# khanh_PB_ip5306_1_1.net
KiCad netlist of a schematic drawn in EAGLE
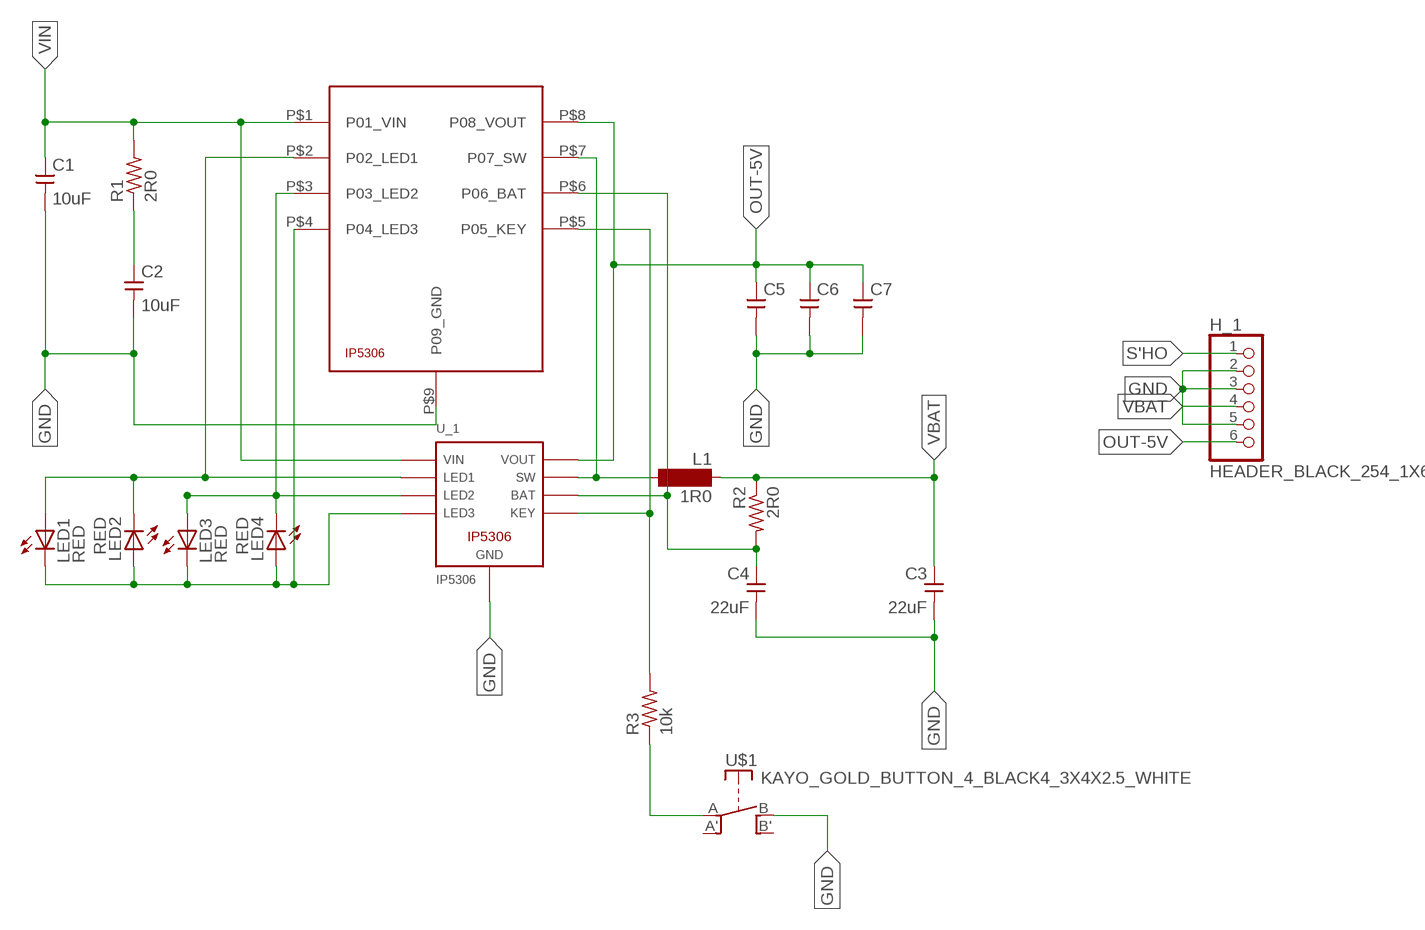
[diagram p0: schematic, sheet 1]

(export (version "E")
  (design (tool "Eeschema 10.0.6"))
  (components
    (comp (ref "C1")
      (value "10uF")
      (footprint "eagle-import:C1206")
      (libsource (lib "eagle-import") (part "KAYO_CAP_CERAMIC_120610UF"))
    )
    (comp (ref "C2")
      (value "10uF")
      (footprint "eagle-import:C1206")
      (libsource (lib "eagle-import") (part "KAYO_CAP_CERAMIC_120610UF"))
    )
    (comp (ref "C3")
      (value "22uF")
      (footprint "eagle-import:C1206")
      (libsource (lib "eagle-import") (part "KAYO_CAP_CERAMIC_120622UF"))
    )
    (comp (ref "C4")
      (value "22uF")
      (footprint "eagle-import:C1206")
      (libsource (lib "eagle-import") (part "KAYO_CAP_CERAMIC_120622UF"))
    )
    (comp (ref "C5")
      (value "KAYO_CAP_CERAMIC22UF_KXN_0603")
      (footprint "eagle-import:KXN_C0603")
      (libsource (lib "eagle-import") (part "KAYO_CAP_CERAMIC_KXN_060322UF"))
    )
    (comp (ref "C6")
      (value "KAYO_CAP_CERAMIC22UF_KXN_0603")
      (footprint "eagle-import:KXN_C0603")
      (libsource (lib "eagle-import") (part "KAYO_CAP_CERAMIC_KXN_060322UF"))
    )
    (comp (ref "C7")
      (value "KAYO_CAP_CERAMIC22UF_KXN_0603")
      (footprint "eagle-import:KXN_C0603")
      (libsource (lib "eagle-import") (part "KAYO_CAP_CERAMIC_KXN_060322UF"))
    )
    (comp (ref "H_1")
      (value "HEADER_BLACK_254_1X6")
      (footprint "eagle-import:HEADER_1X6_254")
      (libsource (lib "eagle-import") (part "KXN_HEADER_1X6"))
    )
    (comp (ref "L1")
      (value "1R0")
      (footprint "eagle-import:CKST_0603_0630_PACK")
      (libsource (lib "eagle-import") (part "INDUCTOR_FEEDER_KAYO_0650"))
    )
    (comp (ref "LED1")
      (value "RED")
      (footprint "eagle-import:KXN_LED_0603")
      (libsource (lib "eagle-import") (part "KAYO_LED_KXN_LED_0603_RED"))
    )
    (comp (ref "LED2")
      (value "RED")
      (footprint "eagle-import:KXN_LED_0603")
      (libsource (lib "eagle-import") (part "KAYO_LED_KXN_LED_0603_RED"))
    )
    (comp (ref "LED3")
      (value "RED")
      (footprint "eagle-import:KXN_LED_0603")
      (libsource (lib "eagle-import") (part "KAYO_LED_KXN_LED_0603_RED"))
    )
    (comp (ref "LED4")
      (value "RED")
      (footprint "eagle-import:KXN_LED_0603")
      (libsource (lib "eagle-import") (part "KAYO_LED_KXN_LED_0603_RED"))
    )
    (comp (ref "R1")
      (value "2R0")
      (footprint "eagle-import:R0603")
      (libsource (lib "eagle-import") (part "R-US_R0603"))
    )
    (comp (ref "R2")
      (value "2R0")
      (footprint "eagle-import:R0603")
      (libsource (lib "eagle-import") (part "R-US_R0603"))
    )
    (comp (ref "R3")
      (value "10k")
      (footprint "eagle-import:R0603")
      (libsource (lib "eagle-import") (part "R-US_R0603"))
    )
    (comp (ref "U$1")
      (value "KAYO_GOLD_BUTTON_4_BLACK4_3X4X2.5_WHITE")
      (footprint "eagle-import:KXN_BUTTON_3_4_2.5MM")
      (libsource (lib "eagle-import") (part "KAYO_GOLD_BUTTON_44_3X4X2.5_WHITE_BLACK"))
    )
    (comp (ref "U$2")
      (value "IP5306")
      (footprint "eagle-import:IP5306")
      (libsource (lib "eagle-import") (part "IP5306"))
    )
    (comp (ref "U_1")
      (value "IP5306")
      (footprint "eagle-import:ESOP8")
      (libsource (lib "eagle-import") (part "IP5306_1"))
    )
  )
  (nets
    (net (code "1") (name "GND") (class "Default")
      (node (ref "C1") (pin "2") (pinfunction "-_2") (pintype "passive"))
      (node (ref "C2") (pin "2") (pinfunction "-_2") (pintype "passive"))
      (node (ref "C3") (pin "2") (pinfunction "-_2") (pintype "passive"))
      (node (ref "C4") (pin "2") (pinfunction "-_2") (pintype "passive"))
      (node (ref "C5") (pin "2") (pinfunction "-_2") (pintype "passive"))
      (node (ref "C6") (pin "2") (pinfunction "-_2") (pintype "passive"))
      (node (ref "C7") (pin "2") (pinfunction "-_2") (pintype "passive"))
      (node (ref "H_1") (pin "2") (pinfunction "2_2") (pintype "passive"))
      (node (ref "H_1") (pin "3") (pinfunction "3_3") (pintype "passive"))
      (node (ref "H_1") (pin "5") (pinfunction "5_5") (pintype "passive"))
      (node (ref "U$1") (pin "B") (pinfunction "B_B") (pintype "passive"))
      (node (ref "U$2") (pin "P$9") (pinfunction "P09_GND_P$9") (pintype "bidirectional"))
      (node (ref "U_1") (pin "9") (pinfunction "P$9_9") (pintype "power_in"))
    )
    (net (code "2") (name "Net-(C2-+)") (class "Default")
      (node (ref "C2") (pin "1") (pinfunction "+_1") (pintype "passive"))
      (node (ref "R1") (pin "1") (pinfunction "1_1") (pintype "passive"))
    )
    (net (code "3") (name "Net-(C4-+)") (class "Default")
      (node (ref "C4") (pin "1") (pinfunction "+_1") (pintype "passive"))
      (node (ref "R2") (pin "2") (pinfunction "2_2") (pintype "passive"))
      (node (ref "U$2") (pin "P$6") (pinfunction "P06_BAT_P$6") (pintype "bidirectional"))
      (node (ref "U_1") (pin "6") (pinfunction "P$6_6") (pintype "bidirectional"))
    )
    (net (code "4") (name "Net-(L1-2)") (class "Default")
      (node (ref "L1") (pin "P$2") (pinfunction "2_P$2") (pintype "passive"))
      (node (ref "U$2") (pin "P$7") (pinfunction "P07_SW_P$7") (pintype "bidirectional"))
      (node (ref "U_1") (pin "7") (pinfunction "P$7_7") (pintype "bidirectional"))
    )
    (net (code "5") (name "Net-(R3-Pad1)") (class "Default")
      (node (ref "R3") (pin "1") (pinfunction "1_1") (pintype "passive"))
      (node (ref "U$1") (pin "A") (pinfunction "A_A") (pintype "passive"))
    )
    (net (code "6") (name "Net-(U$2-P02_LED1)") (class "Default")
      (node (ref "LED1") (pin "A") (pinfunction "A_A") (pintype "passive"))
      (node (ref "LED2") (pin "C") (pinfunction "C_C") (pintype "passive"))
      (node (ref "U$2") (pin "P$2") (pinfunction "P02_LED1_P$2") (pintype "bidirectional"))
      (node (ref "U_1") (pin "2") (pinfunction "P$2_2") (pintype "bidirectional"))
    )
    (net (code "7") (name "Net-(U$2-P03_LED2)") (class "Default")
      (node (ref "LED3") (pin "A") (pinfunction "A_A") (pintype "passive"))
      (node (ref "LED4") (pin "C") (pinfunction "C_C") (pintype "passive"))
      (node (ref "U$2") (pin "P$3") (pinfunction "P03_LED2_P$3") (pintype "bidirectional"))
      (node (ref "U_1") (pin "3") (pinfunction "P$3_3") (pintype "bidirectional"))
    )
    (net (code "8") (name "Net-(U$2-P04_LED3)") (class "Default")
      (node (ref "LED1") (pin "C") (pinfunction "C_C") (pintype "passive"))
      (node (ref "LED2") (pin "A") (pinfunction "A_A") (pintype "passive"))
      (node (ref "LED3") (pin "C") (pinfunction "C_C") (pintype "passive"))
      (node (ref "LED4") (pin "A") (pinfunction "A_A") (pintype "passive"))
      (node (ref "U$2") (pin "P$4") (pinfunction "P04_LED3_P$4") (pintype "bidirectional"))
      (node (ref "U_1") (pin "4") (pinfunction "P$4_4") (pintype "bidirectional"))
    )
    (net (code "9") (name "Net-(U$2-P05_KEY)") (class "Default")
      (node (ref "R3") (pin "2") (pinfunction "2_2") (pintype "passive"))
      (node (ref "U$2") (pin "P$5") (pinfunction "P05_KEY_P$5") (pintype "bidirectional"))
      (node (ref "U_1") (pin "5") (pinfunction "P$5_5") (pintype "bidirectional"))
    )
    (net (code "10") (name "OUT-5V") (class "Default")
      (node (ref "C5") (pin "1") (pinfunction "+_1") (pintype "passive"))
      (node (ref "C6") (pin "1") (pinfunction "+_1") (pintype "passive"))
      (node (ref "C7") (pin "1") (pinfunction "+_1") (pintype "passive"))
      (node (ref "H_1") (pin "6") (pinfunction "6_6") (pintype "passive"))
      (node (ref "U$2") (pin "P$8") (pinfunction "P08_VOUT_P$8") (pintype "bidirectional"))
      (node (ref "U_1") (pin "8") (pinfunction "P$8_8") (pintype "power_in"))
    )
    (net (code "11") (name "S'HO") (class "Default")
      (node (ref "H_1") (pin "1") (pinfunction "1_1") (pintype "passive"))
    )
    (net (code "12") (name "VBAT") (class "Default")
      (node (ref "C3") (pin "1") (pinfunction "+_1") (pintype "passive"))
      (node (ref "H_1") (pin "4") (pinfunction "4_4") (pintype "passive"))
      (node (ref "L1") (pin "P$1") (pinfunction "1_P$1") (pintype "passive"))
      (node (ref "R2") (pin "1") (pinfunction "1_1") (pintype "passive"))
    )
    (net (code "13") (name "VIN") (class "Default")
      (node (ref "C1") (pin "1") (pinfunction "+_1") (pintype "passive"))
      (node (ref "R1") (pin "2") (pinfunction "2_2") (pintype "passive"))
      (node (ref "U$2") (pin "P$1") (pinfunction "P01_VIN_P$1") (pintype "bidirectional"))
      (node (ref "U_1") (pin "1") (pinfunction "P$1_1") (pintype "power_in"))
    )
    (net (code "14") (name "unconnected-(U$1-PadA')") (class "Default")
      (node (ref "U$1") (pin "A'") (pinfunction "A'_A'") (pintype "passive"))
    )
    (net (code "15") (name "unconnected-(U$1-PadB')") (class "Default")
      (node (ref "U$1") (pin "B'") (pinfunction "B'_B'") (pintype "passive"))
    )
  )
)
